# 130808_AriloTX_0_0.net
KiCad netlist of a schematic drawn in EAGLE
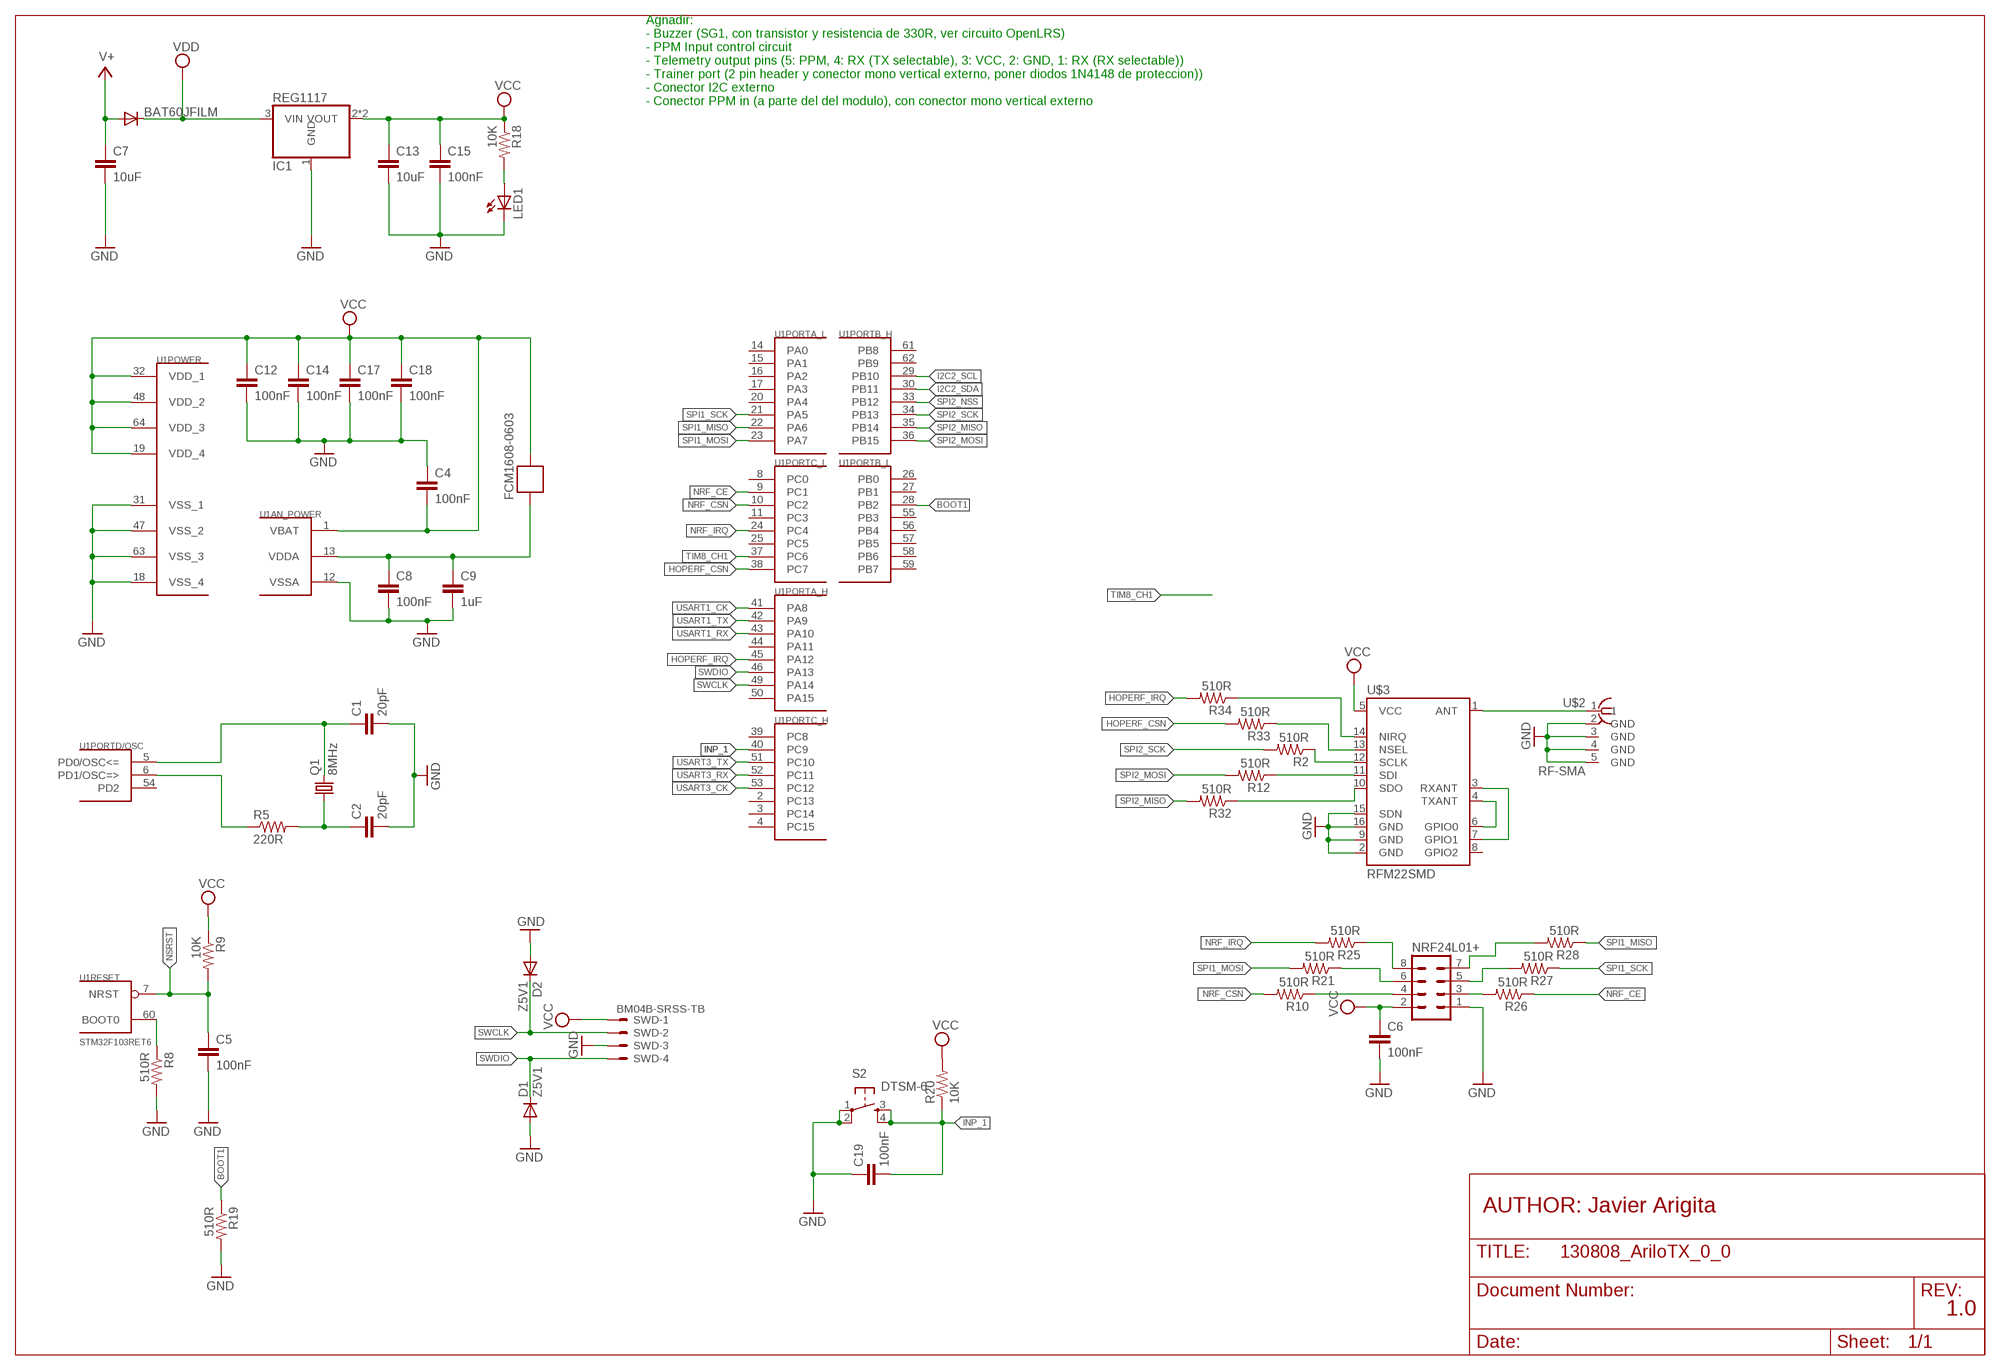
[diagram p0: schematic, sheet 1]

(export (version "E")
  (design (tool "Eeschema 10.0.6"))
  (components
    (comp (ref "BAT60JFILM")
      (value "DIODE-SOD323-R")
      (footprint "eagle-import:SOD323-R")
      (libsource (lib "eagle-import") (part "DIODE-SOD323-R"))
    )
    (comp (ref "C1")
      (value "20pF")
      (footprint "eagle-import:C0805")
      (libsource (lib "eagle-import") (part "C-EUC0805"))
    )
    (comp (ref "C2")
      (value "20pF")
      (footprint "eagle-import:C0805")
      (libsource (lib "eagle-import") (part "C-EUC0805"))
    )
    (comp (ref "C4")
      (value "100nF")
      (footprint "eagle-import:C0805")
      (libsource (lib "eagle-import") (part "C-EUC0805"))
    )
    (comp (ref "C5")
      (value "100nF")
      (footprint "eagle-import:C0805")
      (libsource (lib "eagle-import") (part "C-EUC0805"))
    )
    (comp (ref "C6")
      (value "100nF")
      (footprint "eagle-import:C0805")
      (libsource (lib "eagle-import") (part "C-EUC0805"))
    )
    (comp (ref "C7")
      (value "10uF")
      (footprint "eagle-import:C3216")
      (libsource (lib "eagle-import") (part "resistor_C-EUC3216"))
    )
    (comp (ref "C8")
      (value "100nF")
      (footprint "eagle-import:C0805")
      (libsource (lib "eagle-import") (part "C-EUC0805"))
    )
    (comp (ref "C9")
      (value "1uF")
      (footprint "eagle-import:C3216")
      (libsource (lib "eagle-import") (part "resistor_C-EUC3216"))
    )
    (comp (ref "C12")
      (value "100nF")
      (footprint "eagle-import:C0805")
      (libsource (lib "eagle-import") (part "C-EUC0805"))
    )
    (comp (ref "C13")
      (value "10uF")
      (footprint "eagle-import:C3216")
      (libsource (lib "eagle-import") (part "resistor_C-EUC3216"))
    )
    (comp (ref "C14")
      (value "100nF")
      (footprint "eagle-import:C0805")
      (libsource (lib "eagle-import") (part "C-EUC0805"))
    )
    (comp (ref "C15")
      (value "100nF")
      (footprint "eagle-import:C0805")
      (libsource (lib "eagle-import") (part "C-EUC0805"))
    )
    (comp (ref "C17")
      (value "100nF")
      (footprint "eagle-import:C0805")
      (libsource (lib "eagle-import") (part "C-EUC0805"))
    )
    (comp (ref "C18")
      (value "100nF")
      (footprint "eagle-import:C0805")
      (libsource (lib "eagle-import") (part "C-EUC0805"))
    )
    (comp (ref "C19")
      (value "100nF")
      (footprint "eagle-import:C0805")
      (libsource (lib "eagle-import") (part "C-EUC0805"))
    )
    (comp (ref "D1")
      (value "Z5V1")
      (footprint "eagle-import:SOD323-R")
      (libsource (lib "eagle-import") (part "DIODE-SOD323-R"))
    )
    (comp (ref "D2")
      (value "Z5V1")
      (footprint "eagle-import:SOD323-R")
      (libsource (lib "eagle-import") (part "DIODE-SOD323-R"))
    )
    (comp (ref "FCM1608-0603")
      (value "FERRITE-BEAD")
      (footprint "eagle-import:R0603")
      (libsource (lib "eagle-import") (part "FERRITE-BEAD"))
    )
    (comp (ref "IC1")
      (value "REG1117")
      (footprint "eagle-import:SOT223")
      (libsource (lib "eagle-import") (part "REG1117"))
    )
    (comp (ref "LED1")
      (value "LED0805")
      (footprint "eagle-import:CHIPLED_0805")
      (libsource (lib "eagle-import") (part "LED0805"))
    )
    (comp (ref "NRF24L01+")
      (value "MA04-2")
      (footprint "eagle-import:MA04-2")
      (libsource (lib "eagle-import") (part "MA04-2"))
    )
    (comp (ref "Q1")
      (value "8MHz")
      (footprint "eagle-import:SM49")
      (libsource (lib "eagle-import") (part "CRYSTALSM49"))
    )
    (comp (ref "R2")
      (value "510R")
      (footprint "eagle-import:R0805")
      (libsource (lib "eagle-import") (part "RESISTOR0805"))
    )
    (comp (ref "R5")
      (value "220R")
      (footprint "eagle-import:R0805")
      (libsource (lib "eagle-import") (part "RESISTOR0805"))
    )
    (comp (ref "R8")
      (value "510R")
      (footprint "eagle-import:R0805")
      (libsource (lib "eagle-import") (part "RESISTOR0805"))
    )
    (comp (ref "R9")
      (value "10K")
      (footprint "eagle-import:R0805")
      (libsource (lib "eagle-import") (part "RESISTOR0805"))
    )
    (comp (ref "R10")
      (value "510R")
      (footprint "eagle-import:R0805")
      (libsource (lib "eagle-import") (part "RESISTOR0805"))
    )
    (comp (ref "R12")
      (value "510R")
      (footprint "eagle-import:R0805")
      (libsource (lib "eagle-import") (part "RESISTOR0805"))
    )
    (comp (ref "R18")
      (value "10K")
      (footprint "eagle-import:R0805")
      (libsource (lib "eagle-import") (part "RESISTOR0805"))
    )
    (comp (ref "R19")
      (value "510R")
      (footprint "eagle-import:R0805")
      (libsource (lib "eagle-import") (part "RESISTOR0805"))
    )
    (comp (ref "R20")
      (value "10K")
      (footprint "eagle-import:R0805")
      (libsource (lib "eagle-import") (part "RESISTOR0805"))
    )
    (comp (ref "R21")
      (value "510R")
      (footprint "eagle-import:R0805")
      (libsource (lib "eagle-import") (part "RESISTOR0805"))
    )
    (comp (ref "R25")
      (value "510R")
      (footprint "eagle-import:R0805")
      (libsource (lib "eagle-import") (part "RESISTOR0805"))
    )
    (comp (ref "R26")
      (value "510R")
      (footprint "eagle-import:R0805")
      (libsource (lib "eagle-import") (part "RESISTOR0805"))
    )
    (comp (ref "R27")
      (value "510R")
      (footprint "eagle-import:R0805")
      (libsource (lib "eagle-import") (part "RESISTOR0805"))
    )
    (comp (ref "R28")
      (value "510R")
      (footprint "eagle-import:R0805")
      (libsource (lib "eagle-import") (part "RESISTOR0805"))
    )
    (comp (ref "R32")
      (value "510R")
      (footprint "eagle-import:R0805")
      (libsource (lib "eagle-import") (part "RESISTOR0805"))
    )
    (comp (ref "R33")
      (value "510R")
      (footprint "eagle-import:R0805")
      (libsource (lib "eagle-import") (part "RESISTOR0805"))
    )
    (comp (ref "R34")
      (value "510R")
      (footprint "eagle-import:R0805")
      (libsource (lib "eagle-import") (part "RESISTOR0805"))
    )
    (comp (ref "S2")
      (value "DTSM-6")
      (footprint "eagle-import:DTSM-6")
      (libsource (lib "eagle-import") (part "DTSM-6"))
    )
    (comp (ref "SWD")
      (value "BM04B-SRSS-TB")
      (footprint "eagle-import:BM04B-SRSS-TB")
      (libsource (lib "eagle-import") (part "?M04B-SRSS-TBB"))
    )
    (comp (ref "U$2")
      (value "RF-SMA")
      (footprint "eagle-import:BU-SMA-H")
      (libsource (lib "eagle-import") (part "RF-SMA"))
    )
    (comp (ref "U$3")
      (value "RFM22SMD")
      (footprint "eagle-import:RFM22-XXX-S2")
      (libsource (lib "eagle-import") (part "RFM22SMD"))
    )
    (comp (ref "U1")
      (value "STM32F103RET6")
      (footprint "eagle-import:TQFP64")
      (libsource (lib "eagle-import") (part "STM32F10XRXT6"))
    )
  )
  (nets
    (net (code "1") (name "BOOT1") (class "Default")
      (node (ref "R19") (pin "1") (pinfunction "1_1") (pintype "passive"))
      (node (ref "U1") (pin "28") (pinfunction "PB2_28") (pintype "bidirectional"))
    )
    (net (code "2") (name "GND") (class "Default")
      (node (ref "C1") (pin "2") (pinfunction "2_2") (pintype "passive"))
      (node (ref "C12") (pin "2") (pinfunction "2_2") (pintype "passive"))
      (node (ref "C13") (pin "2") (pinfunction "2_2") (pintype "passive"))
      (node (ref "C14") (pin "2") (pinfunction "2_2") (pintype "passive"))
      (node (ref "C15") (pin "2") (pinfunction "2_2") (pintype "passive"))
      (node (ref "C17") (pin "2") (pinfunction "2_2") (pintype "passive"))
      (node (ref "C18") (pin "2") (pinfunction "2_2") (pintype "passive"))
      (node (ref "C19") (pin "1") (pinfunction "1_1") (pintype "passive"))
      (node (ref "C2") (pin "2") (pinfunction "2_2") (pintype "passive"))
      (node (ref "C4") (pin "1") (pinfunction "1_1") (pintype "passive"))
      (node (ref "C5") (pin "2") (pinfunction "2_2") (pintype "passive"))
      (node (ref "C6") (pin "2") (pinfunction "2_2") (pintype "passive"))
      (node (ref "C7") (pin "2") (pinfunction "2_2") (pintype "passive"))
      (node (ref "C8") (pin "2") (pinfunction "2_2") (pintype "passive"))
      (node (ref "C9") (pin "2") (pinfunction "2_2") (pintype "passive"))
      (node (ref "D1") (pin "A") (pinfunction "A_A") (pintype "passive"))
      (node (ref "D2") (pin "A") (pinfunction "A_A") (pintype "passive"))
      (node (ref "IC1") (pin "1") (pinfunction "GND_1") (pintype "power_in"))
      (node (ref "LED1") (pin "C") (pinfunction "C_C") (pintype "passive"))
      (node (ref "NRF24L01+") (pin "1") (pinfunction "1_1") (pintype "passive"))
      (node (ref "R19") (pin "2") (pinfunction "2_2") (pintype "passive"))
      (node (ref "R8") (pin "2") (pinfunction "2_2") (pintype "passive"))
      (node (ref "S2") (pin "1") (pinfunction "1_1") (pintype "passive"))
      (node (ref "S2") (pin "2") (pinfunction "2_2") (pintype "passive"))
      (node (ref "SWD") (pin "3") (pinfunction "S_3") (pintype "passive"))
      (node (ref "U$2") (pin "2") (pinfunction "GND_2") (pintype "power_in"))
      (node (ref "U$2") (pin "3") (pinfunction "GND_3") (pintype "bidirectional"))
      (node (ref "U$2") (pin "4") (pinfunction "GND_4") (pintype "bidirectional"))
      (node (ref "U$2") (pin "5") (pinfunction "GND_5") (pintype "bidirectional"))
      (node (ref "U$3") (pin "15") (pinfunction "SDN_15") (pintype "input"))
      (node (ref "U$3") (pin "16") (pinfunction "GND_16") (pintype "power_in"))
      (node (ref "U$3") (pin "2") (pinfunction "GND_2") (pintype "power_in"))
      (node (ref "U$3") (pin "9") (pinfunction "GND_9") (pintype "power_in"))
      (node (ref "U1") (pin "12") (pinfunction "VSSA_12") (pintype "power_in"))
      (node (ref "U1") (pin "18") (pinfunction "VSS_4_18") (pintype "power_in"))
      (node (ref "U1") (pin "31") (pinfunction "VSS_1_31") (pintype "power_in"))
      (node (ref "U1") (pin "47") (pinfunction "VSS_2_47") (pintype "power_in"))
      (node (ref "U1") (pin "63") (pinfunction "VSS_3_63") (pintype "power_in"))
    )
    (net (code "3") (name "HOPERF_CSN") (class "Default")
      (node (ref "R33") (pin "2") (pinfunction "2_2") (pintype "passive"))
      (node (ref "U1") (pin "38") (pinfunction "PC7_38") (pintype "bidirectional"))
    )
    (net (code "4") (name "HOPERF_IRQ") (class "Default")
      (node (ref "R34") (pin "2") (pinfunction "2_2") (pintype "passive"))
      (node (ref "U1") (pin "45") (pinfunction "PA12_45") (pintype "bidirectional"))
    )
    (net (code "5") (name "I2C2_SCL") (class "Default")
      (node (ref "U1") (pin "29") (pinfunction "PB10_29") (pintype "bidirectional"))
    )
    (net (code "6") (name "I2C2_SDA") (class "Default")
      (node (ref "U1") (pin "30") (pinfunction "PB11_30") (pintype "bidirectional"))
    )
    (net (code "7") (name "INP_1") (class "Default")
      (node (ref "C19") (pin "2") (pinfunction "2_2") (pintype "passive"))
      (node (ref "R20") (pin "1") (pinfunction "1_1") (pintype "passive"))
      (node (ref "S2") (pin "3") (pinfunction "3_3") (pintype "passive"))
      (node (ref "S2") (pin "4") (pinfunction "4_4") (pintype "passive"))
      (node (ref "U1") (pin "40") (pinfunction "PC9_40") (pintype "bidirectional"))
    )
    (net (code "8") (name "NRF_CE") (class "Default")
      (node (ref "R26") (pin "1") (pinfunction "1_1") (pintype "passive"))
      (node (ref "U1") (pin "9") (pinfunction "PC1_9") (pintype "bidirectional"))
    )
    (net (code "9") (name "NRF_CSN") (class "Default")
      (node (ref "R10") (pin "2") (pinfunction "2_2") (pintype "passive"))
      (node (ref "U1") (pin "10") (pinfunction "PC2_10") (pintype "bidirectional"))
    )
    (net (code "10") (name "NRF_IRQ") (class "Default")
      (node (ref "R25") (pin "2") (pinfunction "2_2") (pintype "passive"))
      (node (ref "U1") (pin "24") (pinfunction "PC4_24") (pintype "bidirectional"))
    )
    (net (code "11") (name "NSRST") (class "Default")
      (node (ref "C5") (pin "1") (pinfunction "1_1") (pintype "passive"))
      (node (ref "R9") (pin "2") (pinfunction "2_2") (pintype "passive"))
      (node (ref "U1") (pin "7") (pinfunction "NRST_7") (pintype "input"))
    )
    (net (code "12") (name "Net-(C2-Pad1)") (class "Default")
      (node (ref "C2") (pin "1") (pinfunction "1_1") (pintype "passive"))
      (node (ref "Q1") (pin "1") (pinfunction "1_1") (pintype "passive"))
      (node (ref "R5") (pin "2") (pinfunction "2_2") (pintype "passive"))
    )
    (net (code "13") (name "Net-(FCM1608-0603-P$2)") (class "Default")
      (node (ref "C8") (pin "1") (pinfunction "1_1") (pintype "passive"))
      (node (ref "C9") (pin "1") (pinfunction "1_1") (pintype "passive"))
      (node (ref "FCM1608-0603") (pin "2") (pinfunction "P$2_2") (pintype "bidirectional"))
      (node (ref "U1") (pin "13") (pinfunction "VDDA_13") (pintype "power_in"))
    )
    (net (code "14") (name "Net-(LED1-PadA)") (class "Default")
      (node (ref "LED1") (pin "A") (pinfunction "A_A") (pintype "passive"))
      (node (ref "R18") (pin "2") (pinfunction "2_2") (pintype "passive"))
    )
    (net (code "15") (name "Net-(NRF24L01+-Pad3)") (class "Default")
      (node (ref "NRF24L01+") (pin "3") (pinfunction "3_3") (pintype "passive"))
      (node (ref "R26") (pin "2") (pinfunction "2_2") (pintype "passive"))
    )
    (net (code "16") (name "Net-(NRF24L01+-Pad4)") (class "Default")
      (node (ref "NRF24L01+") (pin "4") (pinfunction "4_4") (pintype "passive"))
      (node (ref "R10") (pin "1") (pinfunction "1_1") (pintype "passive"))
    )
    (net (code "17") (name "Net-(NRF24L01+-Pad5)") (class "Default")
      (node (ref "NRF24L01+") (pin "5") (pinfunction "5_5") (pintype "passive"))
      (node (ref "R27") (pin "2") (pinfunction "2_2") (pintype "passive"))
    )
    (net (code "18") (name "Net-(NRF24L01+-Pad6)") (class "Default")
      (node (ref "NRF24L01+") (pin "6") (pinfunction "6_6") (pintype "passive"))
      (node (ref "R21") (pin "1") (pinfunction "1_1") (pintype "passive"))
    )
    (net (code "19") (name "Net-(NRF24L01+-Pad7)") (class "Default")
      (node (ref "NRF24L01+") (pin "7") (pinfunction "7_7") (pintype "passive"))
      (node (ref "R28") (pin "2") (pinfunction "2_2") (pintype "passive"))
    )
    (net (code "20") (name "Net-(NRF24L01+-Pad8)") (class "Default")
      (node (ref "NRF24L01+") (pin "8") (pinfunction "8_8") (pintype "passive"))
      (node (ref "R25") (pin "1") (pinfunction "1_1") (pintype "passive"))
    )
    (net (code "21") (name "Net-(U$3-ANT)") (class "Default")
      (node (ref "U$2") (pin "1") (pinfunction "1_1") (pintype "passive"))
      (node (ref "U$3") (pin "1") (pinfunction "ANT_1") (pintype "bidirectional"))
    )
    (net (code "22") (name "Net-(U$3-GPIO0)") (class "Default")
      (node (ref "U$3") (pin "4") (pinfunction "TXANT_4") (pintype "input"))
      (node (ref "U$3") (pin "6") (pinfunction "GPIO0_6") (pintype "bidirectional"))
    )
    (net (code "23") (name "Net-(U$3-GPIO1)") (class "Default")
      (node (ref "U$3") (pin "3") (pinfunction "RXANT_3") (pintype "input"))
      (node (ref "U$3") (pin "7") (pinfunction "GPIO1_7") (pintype "bidirectional"))
    )
    (net (code "24") (name "Net-(U$3-NIRQ)") (class "Default")
      (node (ref "R34") (pin "1") (pinfunction "1_1") (pintype "passive"))
      (node (ref "U$3") (pin "14") (pinfunction "NIRQ_14") (pintype "output"))
    )
    (net (code "25") (name "Net-(U$3-NSEL)") (class "Default")
      (node (ref "R33") (pin "1") (pinfunction "1_1") (pintype "passive"))
      (node (ref "U$3") (pin "13") (pinfunction "NSEL_13") (pintype "input"))
    )
    (net (code "26") (name "Net-(U$3-SCLK)") (class "Default")
      (node (ref "R2") (pin "1") (pinfunction "1_1") (pintype "passive"))
      (node (ref "U$3") (pin "12") (pinfunction "SCLK_12") (pintype "input"))
    )
    (net (code "27") (name "Net-(U$3-SDI)") (class "Default")
      (node (ref "R12") (pin "1") (pinfunction "1_1") (pintype "passive"))
      (node (ref "U$3") (pin "11") (pinfunction "SDI_11") (pintype "input"))
    )
    (net (code "28") (name "Net-(U$3-SDO)") (class "Default")
      (node (ref "R32") (pin "1") (pinfunction "1_1") (pintype "passive"))
      (node (ref "U$3") (pin "10") (pinfunction "SDO_10") (pintype "output"))
    )
    (net (code "29") (name "Net-(U1H-PD0{slash}OSC<=)") (class "Default")
      (node (ref "C1") (pin "1") (pinfunction "1_1") (pintype "passive"))
      (node (ref "Q1") (pin "2") (pinfunction "2_2") (pintype "passive"))
      (node (ref "U1") (pin "5") (pinfunction "PD0/OSC<=_5") (pintype "bidirectional"))
    )
    (net (code "30") (name "Net-(U1H-PD1{slash}OSC=>)") (class "Default")
      (node (ref "R5") (pin "1") (pinfunction "1_1") (pintype "passive"))
      (node (ref "U1") (pin "6") (pinfunction "PD1/OSC=>_6") (pintype "bidirectional"))
    )
    (net (code "31") (name "Net-(U1J-BOOT0)") (class "Default")
      (node (ref "R8") (pin "1") (pinfunction "1_1") (pintype "passive"))
      (node (ref "U1") (pin "60") (pinfunction "BOOT0_60") (pintype "input"))
    )
    (net (code "32") (name "SPI1_MISO") (class "Default")
      (node (ref "R28") (pin "1") (pinfunction "1_1") (pintype "passive"))
      (node (ref "U1") (pin "22") (pinfunction "PA6_22") (pintype "bidirectional"))
    )
    (net (code "33") (name "SPI1_MOSI") (class "Default")
      (node (ref "R21") (pin "2") (pinfunction "2_2") (pintype "passive"))
      (node (ref "U1") (pin "23") (pinfunction "PA7_23") (pintype "bidirectional"))
    )
    (net (code "34") (name "SPI1_SCK") (class "Default")
      (node (ref "R27") (pin "1") (pinfunction "1_1") (pintype "passive"))
      (node (ref "U1") (pin "21") (pinfunction "PA5_21") (pintype "bidirectional"))
    )
    (net (code "35") (name "SPI2_MISO") (class "Default")
      (node (ref "R32") (pin "2") (pinfunction "2_2") (pintype "passive"))
      (node (ref "U1") (pin "35") (pinfunction "PB14_35") (pintype "bidirectional"))
    )
    (net (code "36") (name "SPI2_MOSI") (class "Default")
      (node (ref "R12") (pin "2") (pinfunction "2_2") (pintype "passive"))
      (node (ref "U1") (pin "36") (pinfunction "PB15_36") (pintype "bidirectional"))
    )
    (net (code "37") (name "SPI2_NSS") (class "Default")
      (node (ref "U1") (pin "33") (pinfunction "PB12_33") (pintype "bidirectional"))
    )
    (net (code "38") (name "SPI2_SCK") (class "Default")
      (node (ref "R2") (pin "2") (pinfunction "2_2") (pintype "passive"))
      (node (ref "U1") (pin "34") (pinfunction "PB13_34") (pintype "bidirectional"))
    )
    (net (code "39") (name "SWCLK") (class "Default")
      (node (ref "D2") (pin "C") (pinfunction "C_C") (pintype "passive"))
      (node (ref "SWD") (pin "2") (pinfunction "S_2") (pintype "passive"))
      (node (ref "U1") (pin "49") (pinfunction "PA14_49") (pintype "bidirectional"))
    )
    (net (code "40") (name "SWDIO") (class "Default")
      (node (ref "D1") (pin "C") (pinfunction "C_C") (pintype "passive"))
      (node (ref "SWD") (pin "4") (pinfunction "S_4") (pintype "passive"))
      (node (ref "U1") (pin "46") (pinfunction "PA13_46") (pintype "bidirectional"))
    )
    (net (code "41") (name "TIM8_CH1") (class "Default")
      (node (ref "U1") (pin "37") (pinfunction "PC6_37") (pintype "bidirectional"))
    )
    (net (code "42") (name "USART1_CK") (class "Default")
      (node (ref "U1") (pin "41") (pinfunction "PA8_41") (pintype "bidirectional"))
    )
    (net (code "43") (name "USART1_RX") (class "Default")
      (node (ref "U1") (pin "43") (pinfunction "PA10_43") (pintype "bidirectional"))
    )
    (net (code "44") (name "USART1_TX") (class "Default")
      (node (ref "U1") (pin "42") (pinfunction "PA9_42") (pintype "bidirectional"))
    )
    (net (code "45") (name "USART3_CK") (class "Default")
      (node (ref "U1") (pin "53") (pinfunction "PC12_53") (pintype "bidirectional"))
    )
    (net (code "46") (name "USART3_RX") (class "Default")
      (node (ref "U1") (pin "52") (pinfunction "PC11_52") (pintype "bidirectional"))
    )
    (net (code "47") (name "USART3_TX") (class "Default")
      (node (ref "U1") (pin "51") (pinfunction "PC10_51") (pintype "bidirectional"))
    )
    (net (code "48") (name "V+") (class "Default")
      (node (ref "BAT60JFILM") (pin "A") (pinfunction "A_A") (pintype "passive"))
      (node (ref "C7") (pin "1") (pinfunction "1_1") (pintype "passive"))
    )
    (net (code "49") (name "VCC") (class "Default")
      (node (ref "C12") (pin "1") (pinfunction "1_1") (pintype "passive"))
      (node (ref "C13") (pin "1") (pinfunction "1_1") (pintype "passive"))
      (node (ref "C14") (pin "1") (pinfunction "1_1") (pintype "passive"))
      (node (ref "C15") (pin "1") (pinfunction "1_1") (pintype "passive"))
      (node (ref "C17") (pin "1") (pinfunction "1_1") (pintype "passive"))
      (node (ref "C18") (pin "1") (pinfunction "1_1") (pintype "passive"))
      (node (ref "C4") (pin "2") (pinfunction "2_2") (pintype "passive"))
      (node (ref "C6") (pin "1") (pinfunction "1_1") (pintype "passive"))
      (node (ref "FCM1608-0603") (pin "1") (pinfunction "P$1_1") (pintype "bidirectional"))
      (node (ref "IC1") (pin "2") (pinfunction "VOUT_2") (pintype "power_in"))
      (node (ref "IC1") (pin "4") (pinfunction "VOUT_4") (pintype "power_in"))
      (node (ref "NRF24L01+") (pin "2") (pinfunction "2_2") (pintype "passive"))
      (node (ref "R18") (pin "1") (pinfunction "1_1") (pintype "passive"))
      (node (ref "R20") (pin "2") (pinfunction "2_2") (pintype "passive"))
      (node (ref "R9") (pin "1") (pinfunction "1_1") (pintype "passive"))
      (node (ref "SWD") (pin "1") (pinfunction "S_1") (pintype "passive"))
      (node (ref "U$3") (pin "5") (pinfunction "VCC_5") (pintype "bidirectional"))
      (node (ref "U1") (pin "1") (pinfunction "VBAT_1") (pintype "power_in"))
      (node (ref "U1") (pin "19") (pinfunction "VDD_4_19") (pintype "power_in"))
      (node (ref "U1") (pin "32") (pinfunction "VDD_1_32") (pintype "power_in"))
      (node (ref "U1") (pin "48") (pinfunction "VDD_2_48") (pintype "power_in"))
      (node (ref "U1") (pin "64") (pinfunction "VDD_3_64") (pintype "power_in"))
    )
    (net (code "50") (name "VDD") (class "Default")
      (node (ref "BAT60JFILM") (pin "C") (pinfunction "C_C") (pintype "passive"))
      (node (ref "IC1") (pin "3") (pinfunction "VIN_3") (pintype "input"))
    )
    (net (code "51") (name "unconnected-(U$3-GPIO2-Pad8)") (class "Default")
      (node (ref "U$3") (pin "8") (pinfunction "GPIO2_8") (pintype "bidirectional"))
    )
    (net (code "52") (name "unconnected-(U1B-PA11-Pad44)") (class "Default")
      (node (ref "U1") (pin "44") (pinfunction "PA11_44") (pintype "bidirectional"))
    )
    (net (code "53") (name "unconnected-(U1B-PA15-Pad50)") (class "Default")
      (node (ref "U1") (pin "50") (pinfunction "PA15_50") (pintype "bidirectional"))
    )
    (net (code "54") (name "unconnected-(U1C-PA0-Pad14)") (class "Default")
      (node (ref "U1") (pin "14") (pinfunction "PA0_14") (pintype "bidirectional"))
    )
    (net (code "55") (name "unconnected-(U1C-PA1-Pad15)") (class "Default")
      (node (ref "U1") (pin "15") (pinfunction "PA1_15") (pintype "bidirectional"))
    )
    (net (code "56") (name "unconnected-(U1C-PA2-Pad16)") (class "Default")
      (node (ref "U1") (pin "16") (pinfunction "PA2_16") (pintype "bidirectional"))
    )
    (net (code "57") (name "unconnected-(U1C-PA3-Pad17)") (class "Default")
      (node (ref "U1") (pin "17") (pinfunction "PA3_17") (pintype "bidirectional"))
    )
    (net (code "58") (name "unconnected-(U1C-PA4-Pad20)") (class "Default")
      (node (ref "U1") (pin "20") (pinfunction "PA4_20") (pintype "bidirectional"))
    )
    (net (code "59") (name "unconnected-(U1D-PB8-Pad61)") (class "Default")
      (node (ref "U1") (pin "61") (pinfunction "PB8_61") (pintype "bidirectional"))
    )
    (net (code "60") (name "unconnected-(U1D-PB9-Pad62)") (class "Default")
      (node (ref "U1") (pin "62") (pinfunction "PB9_62") (pintype "bidirectional"))
    )
    (net (code "61") (name "unconnected-(U1E-PB0-Pad26)") (class "Default")
      (node (ref "U1") (pin "26") (pinfunction "PB0_26") (pintype "bidirectional"))
    )
    (net (code "62") (name "unconnected-(U1E-PB1-Pad27)") (class "Default")
      (node (ref "U1") (pin "27") (pinfunction "PB1_27") (pintype "bidirectional"))
    )
    (net (code "63") (name "unconnected-(U1E-PB3-Pad55)") (class "Default")
      (node (ref "U1") (pin "55") (pinfunction "PB3_55") (pintype "bidirectional"))
    )
    (net (code "64") (name "unconnected-(U1E-PB4-Pad56)") (class "Default")
      (node (ref "U1") (pin "56") (pinfunction "PB4_56") (pintype "bidirectional"))
    )
    (net (code "65") (name "unconnected-(U1E-PB5-Pad57)") (class "Default")
      (node (ref "U1") (pin "57") (pinfunction "PB5_57") (pintype "bidirectional"))
    )
    (net (code "66") (name "unconnected-(U1E-PB6-Pad58)") (class "Default")
      (node (ref "U1") (pin "58") (pinfunction "PB6_58") (pintype "bidirectional"))
    )
    (net (code "67") (name "unconnected-(U1E-PB7-Pad59)") (class "Default")
      (node (ref "U1") (pin "59") (pinfunction "PB7_59") (pintype "bidirectional"))
    )
    (net (code "68") (name "unconnected-(U1F-PC8-Pad39)") (class "Default")
      (node (ref "U1") (pin "39") (pinfunction "PC8_39") (pintype "bidirectional"))
    )
    (net (code "69") (name "unconnected-(U1F-PC13-Pad2)") (class "Default")
      (node (ref "U1") (pin "2") (pinfunction "PC13_2") (pintype "bidirectional"))
    )
    (net (code "70") (name "unconnected-(U1F-PC14-Pad3)") (class "Default")
      (node (ref "U1") (pin "3") (pinfunction "PC14_3") (pintype "bidirectional"))
    )
    (net (code "71") (name "unconnected-(U1F-PC15-Pad4)") (class "Default")
      (node (ref "U1") (pin "4") (pinfunction "PC15_4") (pintype "bidirectional"))
    )
    (net (code "72") (name "unconnected-(U1G-PC0-Pad8)") (class "Default")
      (node (ref "U1") (pin "8") (pinfunction "PC0_8") (pintype "bidirectional"))
    )
    (net (code "73") (name "unconnected-(U1G-PC3-Pad11)") (class "Default")
      (node (ref "U1") (pin "11") (pinfunction "PC3_11") (pintype "bidirectional"))
    )
    (net (code "74") (name "unconnected-(U1G-PC5-Pad25)") (class "Default")
      (node (ref "U1") (pin "25") (pinfunction "PC5_25") (pintype "bidirectional"))
    )
    (net (code "75") (name "unconnected-(U1H-PD2-Pad54)") (class "Default")
      (node (ref "U1") (pin "54") (pinfunction "PD2_54") (pintype "bidirectional"))
    )
  )
)
